# Power.net
KiCad netlist of a schematic drawn in Altium Designer
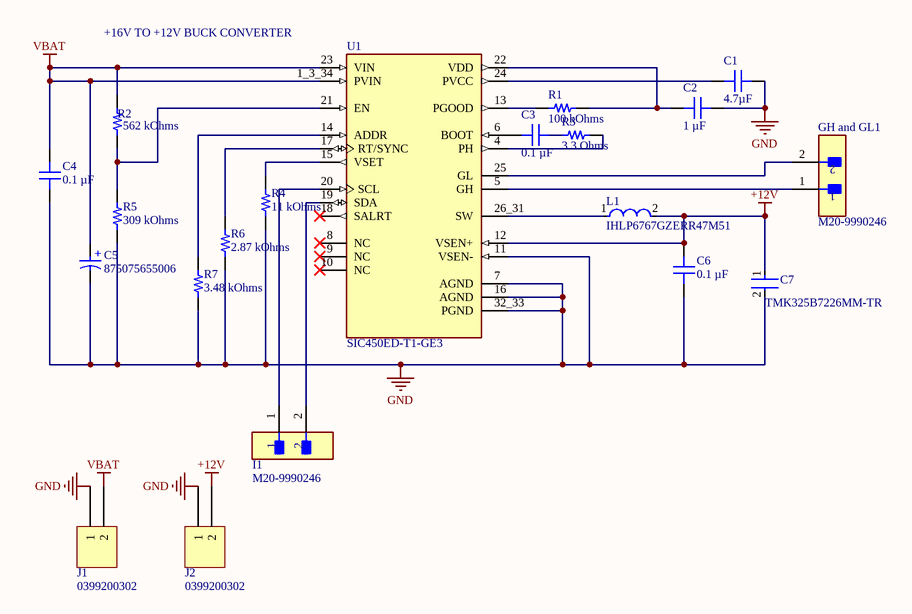
[diagram p0: Power.SchDoc]

(export (version "E")
  (design (tool "Eeschema 10.0.6"))
  (components
    (comp (ref "C1")
      (value "4.7µF")
      (footprint "CAP 0603_1608")
      (description "CAP CER 4.7UF 6.3V X5R 0603")
      (fields (field (name "PART NUMBER") "06036D475KAT4A") (field (name "MANUFACTURER") "AVX Corporation"))
      (libsource (lib "Celestial Altium Library - altium_library (2)") (part "Capacitor"))
    )
    (comp (ref "C2")
      (value "1 µF")
      (footprint "CAP 0603_1608")
      (description "CAP CER 1UF 6.3V X7R 0603")
      (fields (field (name "PART NUMBER") "C0603X105M9RACAUTO") (field (name "MANUFACTURER") "KEMET"))
      (libsource (lib "Celestial Altium Library - altium_library (2)") (part "Capacitor"))
    )
    (comp (ref "C3")
      (value "0.1 µF")
      (footprint "CAP 0402_1005")
      (description "CAP CER 100NF 10V X7R 0402")
      (fields
        (field (name "PART NUMBER") "CL05B104KP5VPNC")
        (field (name "MANUFACTURER") "Samsung Electro-Mechanics")
      )
      (libsource (lib "Celestial Altium Library - altium_library (2)") (part "Capacitor"))
    )
    (comp (ref "C4")
      (value "0.1 µF")
      (footprint "CAP 0402_1005")
      (description "CAP CER 0.1UF 25V X7R 0402")
      (fields
        (field (name "PART NUMBER") "GCM155R71E104KE02D")
        (field (name "MANUFACTURER") "Murata Electronics")
      )
      (libsource (lib "Celestial Altium Library - altium_library (2)") (part "Capacitor"))
    )
    (comp (ref "C5")
      (value "875075655006")
      (footprint "WCAP-PSLC_D8H11.7")
      (description "875075655006 Cap, 150Uf, 35V, Alu Elec Smd, Polymer Rohs Compliant: Yes")
      (libsource (lib "Altium Content Vault") (part "Capacitor_Polarized"))
    )
    (comp (ref "C6")
      (value "0.1 µF")
      (footprint "CAP 0402_1005")
      (description "CAP CER 0.1UF 25V X7R 0402")
      (fields
        (field (name "PART NUMBER") "GCM155R71E104KE02D")
        (field (name "MANUFACTURER") "Murata Electronics")
      )
      (libsource (lib "Celestial Altium Library - altium_library (2)") (part "Capacitor"))
    )
    (comp (ref "C7")
      (value "TMK325B7226MM-TR")
      (footprint "FP-1210-L_3_2_0_3-W_2_5_0-MFG")
      (description "CAP CER 22UF 25V X7R 1210")
      (fields (field (name "TOLERANCE") "20%") (field (name "VOLTAGE") "25V"))
      (libsource (lib "Altium Content Vault") (part "b4654b650e69147ec39a6b967a45e02"))
    )
    (comp (ref "GH and GL1")
      (value "M20-9990246")
      (footprint "FP-M20-9990246-MFG")
      (description "CONN HEADER VERT 2POS 2.54MM")
      (fields
        (field (name "OCTOPART") "https://octopart.com/m20-9990246-harwin-2590635")
        (field (name "MANUFACTURER") "Harwin")
      )
      (libsource (lib "") (part "3bc925449376181038e59eaffc5286c_1"))
    )
    (comp (ref "I1")
      (value "M20-9990246")
      (footprint "FP-M20-9990246-MFG")
      (description "CONN HEADER VERT 2POS 2.54MM")
      (fields
        (field (name "OCTOPART") "https://octopart.com/m20-9990246-harwin-2590635")
        (field (name "MANUFACTURER") "Harwin")
      )
      (libsource (lib "Altium Content Vault") (part "3bc925449376181038e59eaffc5286c"))
    )
    (comp (ref "J1")
      (value "0399200302")
      (footprint "MOLEX 0399200302")
      (description "TERM BLK 2P SIDE ENTRY 15MM PCB")
      (fields (field (name "MANUFACTURER") "Molex") (field (name "VOLTAGE") "600 V"))
      (libsource (lib "Celestial Altium Library - altium_library (2)") (part "2 Pin"))
    )
    (comp (ref "J2")
      (value "0399200302")
      (footprint "MOLEX 0399200302")
      (description "TERM BLK 2P SIDE ENTRY 15MM PCB")
      (fields (field (name "MANUFACTURER") "Molex") (field (name "VOLTAGE") "600 V"))
      (libsource (lib "Celestial Altium Library - altium_library (2)") (part "2 Pin"))
    )
    (comp (ref "L1")
      (value "IHLP6767GZERR47M51")
      (footprint "FP-IHLP-6767GZ-FP_3_825x1-MFG")
      (description "Commercial Inductors, High Temperature (155 °C) Series 0.47uH 65A 0.95mΩ 20%")
      (fields (field (name "TOLERANCE") "20%"))
      (libsource (lib "Altium Content Vault") (part "725321dda6339637d4d059423bc1c3c"))
    )
    (comp (ref "R1")
      (value "100 kOhms")
      (footprint "RES 0402_1005")
      (description "RES SMD 100K OHM 1% 1/16W 0402")
      (fields (field (name "PART NUMBER") "RT0402FRE07100KL") (field (name "MANUFACTURER") "Yageo"))
      (libsource (lib "Celestial Altium Library - altium_library (2)") (part "Resistor"))
    )
    (comp (ref "R2")
      (value "562 kOhms")
      (footprint "RES 0603_1608")
      (description "RES 562K OHM 1% 1/10W 0603")
      (fields
        (field (name "PART NUMBER") "RK73H1JTTD5623F")
        (field (name "MANUFACTURER") "KOA Speer Electronics, Inc.")
      )
      (libsource (lib "Celestial Altium Library - altium_library (2)") (part "Resistor"))
    )
    (comp (ref "R3")
      (value "3.3 Ohms")
      (footprint "RES 0402_1005")
      (description "RES SMD 3.3 OHM 5% 1/10W 0402")
      (fields
        (field (name "PART NUMBER") "ERJ-2GEJ3R3X")
        (field (name "MANUFACTURER") "Panasonic Electronic Components")
      )
      (libsource (lib "Celestial Altium Library - altium_library (2)") (part "Resistor"))
    )
    (comp (ref "R4")
      (value "11 kOhms")
      (footprint "RES 0603_1608")
      (description "RES 11K OHM 0.1% 1/10W 0603")
      (fields (field (name "PART NUMBER") "TNPW060311K0BYEN") (field (name "MANUFACTURER") "Vishay Dale"))
      (libsource (lib "Celestial Altium Library - altium_library (2)") (part "Resistor"))
    )
    (comp (ref "R5")
      (value "309 kOhms")
      (footprint "RES 0603_1608")
      (description "RES SMD 309K OHM 0.1% 1/10W 0603")
      (fields (field (name "PART NUMBER") "RG1608P-3093-B-T5") (field (name "MANUFACTURER") "Susumu"))
      (libsource (lib "Celestial Altium Library - altium_library (2)") (part "Resistor"))
    )
    (comp (ref "R6")
      (value "2.87 kOhms")
      (footprint "RES 0603_1608")
      (description "RES 2.87K OHM 1% 1/10W 0603")
      (fields (field (name "PART NUMBER") "RC0603FR-072K87L") (field (name "MANUFACTURER") "Yageo"))
      (libsource (lib "Celestial Altium Library - altium_library (2)") (part "Resistor"))
    )
    (comp (ref "R7")
      (value "3.48 kOhms")
      (footprint "RES 0603_1608")
      (description "RES 3.48K OHM 1% 1/8W 0603")
      (fields
        (field (name "PART NUMBER") "RNCP0603FTD3K48")
        (field (name "MANUFACTURER") "Stackpole Electronics Inc")
      )
      (libsource (lib "Celestial Altium Library - altium_library (2)") (part "Resistor"))
    )
    (comp (ref "U1")
      (value "SIC450ED-T1-GE3")
      (footprint "VREG_SIC450ED-T1-GE3")
      (description "Buck Switching Regulator IC Positive Adjustable 0.3V 1 Output 40A 34-PowerWFQFN")
      (fields (field (name "MF") "Vishay Siliconix"))
      (libsource (lib "Americas- Environmental Engineering Club- University of Victoria") (part "SIC450ED-T1-GE3"))
    )
  )
  (nets
    (net (code "1") (name "+12V") (class "Default")
      (node (ref "C6") (pin "2") (pinfunction "2_2") (pintype "passive"))
      (node (ref "C7") (pin "1") (pinfunction "1_1") (pintype "passive"))
      (node (ref "J2") (pin "2") (pinfunction "2_2") (pintype "passive"))
      (node (ref "L1") (pin "2") (pinfunction "2_2") (pintype "passive"))
      (node (ref "U1") (pin "12") (pinfunction "VSEN+_12") (pintype "input"))
    )
    (net (code "2") (name "GND") (class "Default")
      (node (ref "C1") (pin "1") (pinfunction "1_1") (pintype "passive"))
      (node (ref "C2") (pin "1") (pinfunction "1_1") (pintype "passive"))
      (node (ref "C4") (pin "1") (pinfunction "1_1") (pintype "passive"))
      (node (ref "C5") (pin "2") (pinfunction "N_2") (pintype "passive"))
      (node (ref "C6") (pin "1") (pinfunction "1_1") (pintype "passive"))
      (node (ref "C7") (pin "2") (pinfunction "2_2") (pintype "passive"))
      (node (ref "J1") (pin "1") (pinfunction "1_1") (pintype "passive"))
      (node (ref "J2") (pin "1") (pinfunction "1_1") (pintype "passive"))
      (node (ref "R4") (pin "1") (pinfunction "1_1") (pintype "passive"))
      (node (ref "R5") (pin "1") (pinfunction "1_1") (pintype "passive"))
      (node (ref "R6") (pin "1") (pinfunction "1_1") (pintype "passive"))
      (node (ref "R7") (pin "1") (pinfunction "1_1") (pintype "passive"))
      (node (ref "U1") (pin "11") (pinfunction "VSEN-_11") (pintype "input"))
      (node (ref "U1") (pin "16") (pinfunction "AGND_16") (pintype "power_in"))
      (node (ref "U1") (pin "32_33") (pinfunction "PGND_32_33") (pintype "power_in"))
      (node (ref "U1") (pin "7") (pinfunction "AGND_7") (pintype "power_in"))
    )
    (net (code "3") (name "Net-(C3-Pad2)") (class "Default")
      (node (ref "C3") (pin "2") (pinfunction "2_2") (pintype "passive"))
      (node (ref "R3") (pin "1") (pinfunction "1_1") (pintype "passive"))
    )
    (net (code "4") (name "Net-(U1-ADDR)") (class "Default")
      (node (ref "R7") (pin "2") (pinfunction "2_2") (pintype "passive"))
      (node (ref "U1") (pin "14") (pinfunction "ADDR_14") (pintype "input"))
    )
    (net (code "5") (name "Net-(U1-BOOT)") (class "Default")
      (node (ref "C3") (pin "1") (pinfunction "1_1") (pintype "passive"))
      (node (ref "U1") (pin "6") (pinfunction "BOOT_6") (pintype "input"))
    )
    (net (code "6") (name "Net-(U1-EN)") (class "Default")
      (node (ref "R2") (pin "1") (pinfunction "1_1") (pintype "passive"))
      (node (ref "R5") (pin "2") (pinfunction "2_2") (pintype "passive"))
      (node (ref "U1") (pin "21") (pinfunction "EN_21") (pintype "input"))
    )
    (net (code "7") (name "Net-(U1-GH)") (class "Default")
      (node (ref "GH and GL1") (pin "1") (pinfunction "1_1") (pintype "passive"))
      (node (ref "U1") (pin "5") (pinfunction "GH_5") (pintype "passive"))
    )
    (net (code "8") (name "Net-(U1-GL)") (class "Default")
      (node (ref "GH and GL1") (pin "2") (pinfunction "2_2") (pintype "passive"))
      (node (ref "U1") (pin "25") (pinfunction "GL_25") (pintype "passive"))
    )
    (net (code "9") (name "Net-(U1-PGOOD)") (class "Default")
      (node (ref "R1") (pin "2") (pinfunction "2_2") (pintype "passive"))
      (node (ref "U1") (pin "13") (pinfunction "PGOOD_13") (pintype "output"))
    )
    (net (code "10") (name "Net-(U1-PH)") (class "Default")
      (node (ref "R3") (pin "2") (pinfunction "2_2") (pintype "passive"))
      (node (ref "U1") (pin "4") (pinfunction "PH_4") (pintype "output"))
    )
    (net (code "11") (name "Net-(U1-PVCC)") (class "Default")
      (node (ref "C1") (pin "2") (pinfunction "2_2") (pintype "passive"))
      (node (ref "U1") (pin "24") (pinfunction "PVCC_24") (pintype "output"))
    )
    (net (code "12") (name "Net-(U1-RT{slash}SYNC)") (class "Default")
      (node (ref "R6") (pin "2") (pinfunction "2_2") (pintype "passive"))
      (node (ref "U1") (pin "17") (pinfunction "RT/SYNC_17") (pintype "bidirectional"))
    )
    (net (code "13") (name "Net-(U1-SCL)") (class "Default")
      (node (ref "I1") (pin "1") (pinfunction "1_1") (pintype "passive"))
      (node (ref "U1") (pin "20") (pinfunction "SCL_20") (pintype "input"))
    )
    (net (code "14") (name "Net-(U1-SDA)") (class "Default")
      (node (ref "I1") (pin "2") (pinfunction "2_2") (pintype "passive"))
      (node (ref "U1") (pin "19") (pinfunction "SDA_19") (pintype "bidirectional"))
    )
    (net (code "15") (name "Net-(U1-SW)") (class "Default")
      (node (ref "L1") (pin "1") (pinfunction "1_1") (pintype "passive"))
      (node (ref "U1") (pin "26_31") (pinfunction "SW_26_31") (pintype "passive"))
    )
    (net (code "16") (name "Net-(U1-VDD)") (class "Default")
      (node (ref "C2") (pin "2") (pinfunction "2_2") (pintype "passive"))
      (node (ref "R1") (pin "1") (pinfunction "1_1") (pintype "passive"))
      (node (ref "U1") (pin "22") (pinfunction "VDD_22") (pintype "output"))
    )
    (net (code "17") (name "Net-(U1-VSET)") (class "Default")
      (node (ref "R4") (pin "2") (pinfunction "2_2") (pintype "passive"))
      (node (ref "U1") (pin "15") (pinfunction "VSET_15") (pintype "output"))
    )
    (net (code "18") (name "VBAT") (class "Default")
      (node (ref "C4") (pin "2") (pinfunction "2_2") (pintype "passive"))
      (node (ref "C5") (pin "1") (pinfunction "P_1") (pintype "passive"))
      (node (ref "J1") (pin "2") (pinfunction "2_2") (pintype "passive"))
      (node (ref "R2") (pin "2") (pinfunction "2_2") (pintype "passive"))
      (node (ref "U1") (pin "1_3_34") (pinfunction "PVIN_1_3_34") (pintype "input"))
      (node (ref "U1") (pin "23") (pinfunction "VIN_23") (pintype "input"))
    )
    (net (code "19") (name "unconnected-(U1-NC-Pad8)") (class "Default")
      (node (ref "U1") (pin "8") (pinfunction "NC_8") (pintype "passive+no_connect"))
    )
    (net (code "20") (name "unconnected-(U1-NC-Pad9)") (class "Default")
      (node (ref "U1") (pin "9") (pinfunction "NC_9") (pintype "passive+no_connect"))
    )
    (net (code "21") (name "unconnected-(U1-NC-Pad10)") (class "Default")
      (node (ref "U1") (pin "10") (pinfunction "NC_10") (pintype "passive+no_connect"))
    )
    (net (code "22") (name "unconnected-(U1-SALRT-Pad18)") (class "Default")
      (node (ref "U1") (pin "18") (pinfunction "SALRT_18") (pintype "output+no_connect"))
    )
  )
)
